# RA8D2_MCU_-_Power.net
KiCad netlist of a schematic drawn in Altium Designer
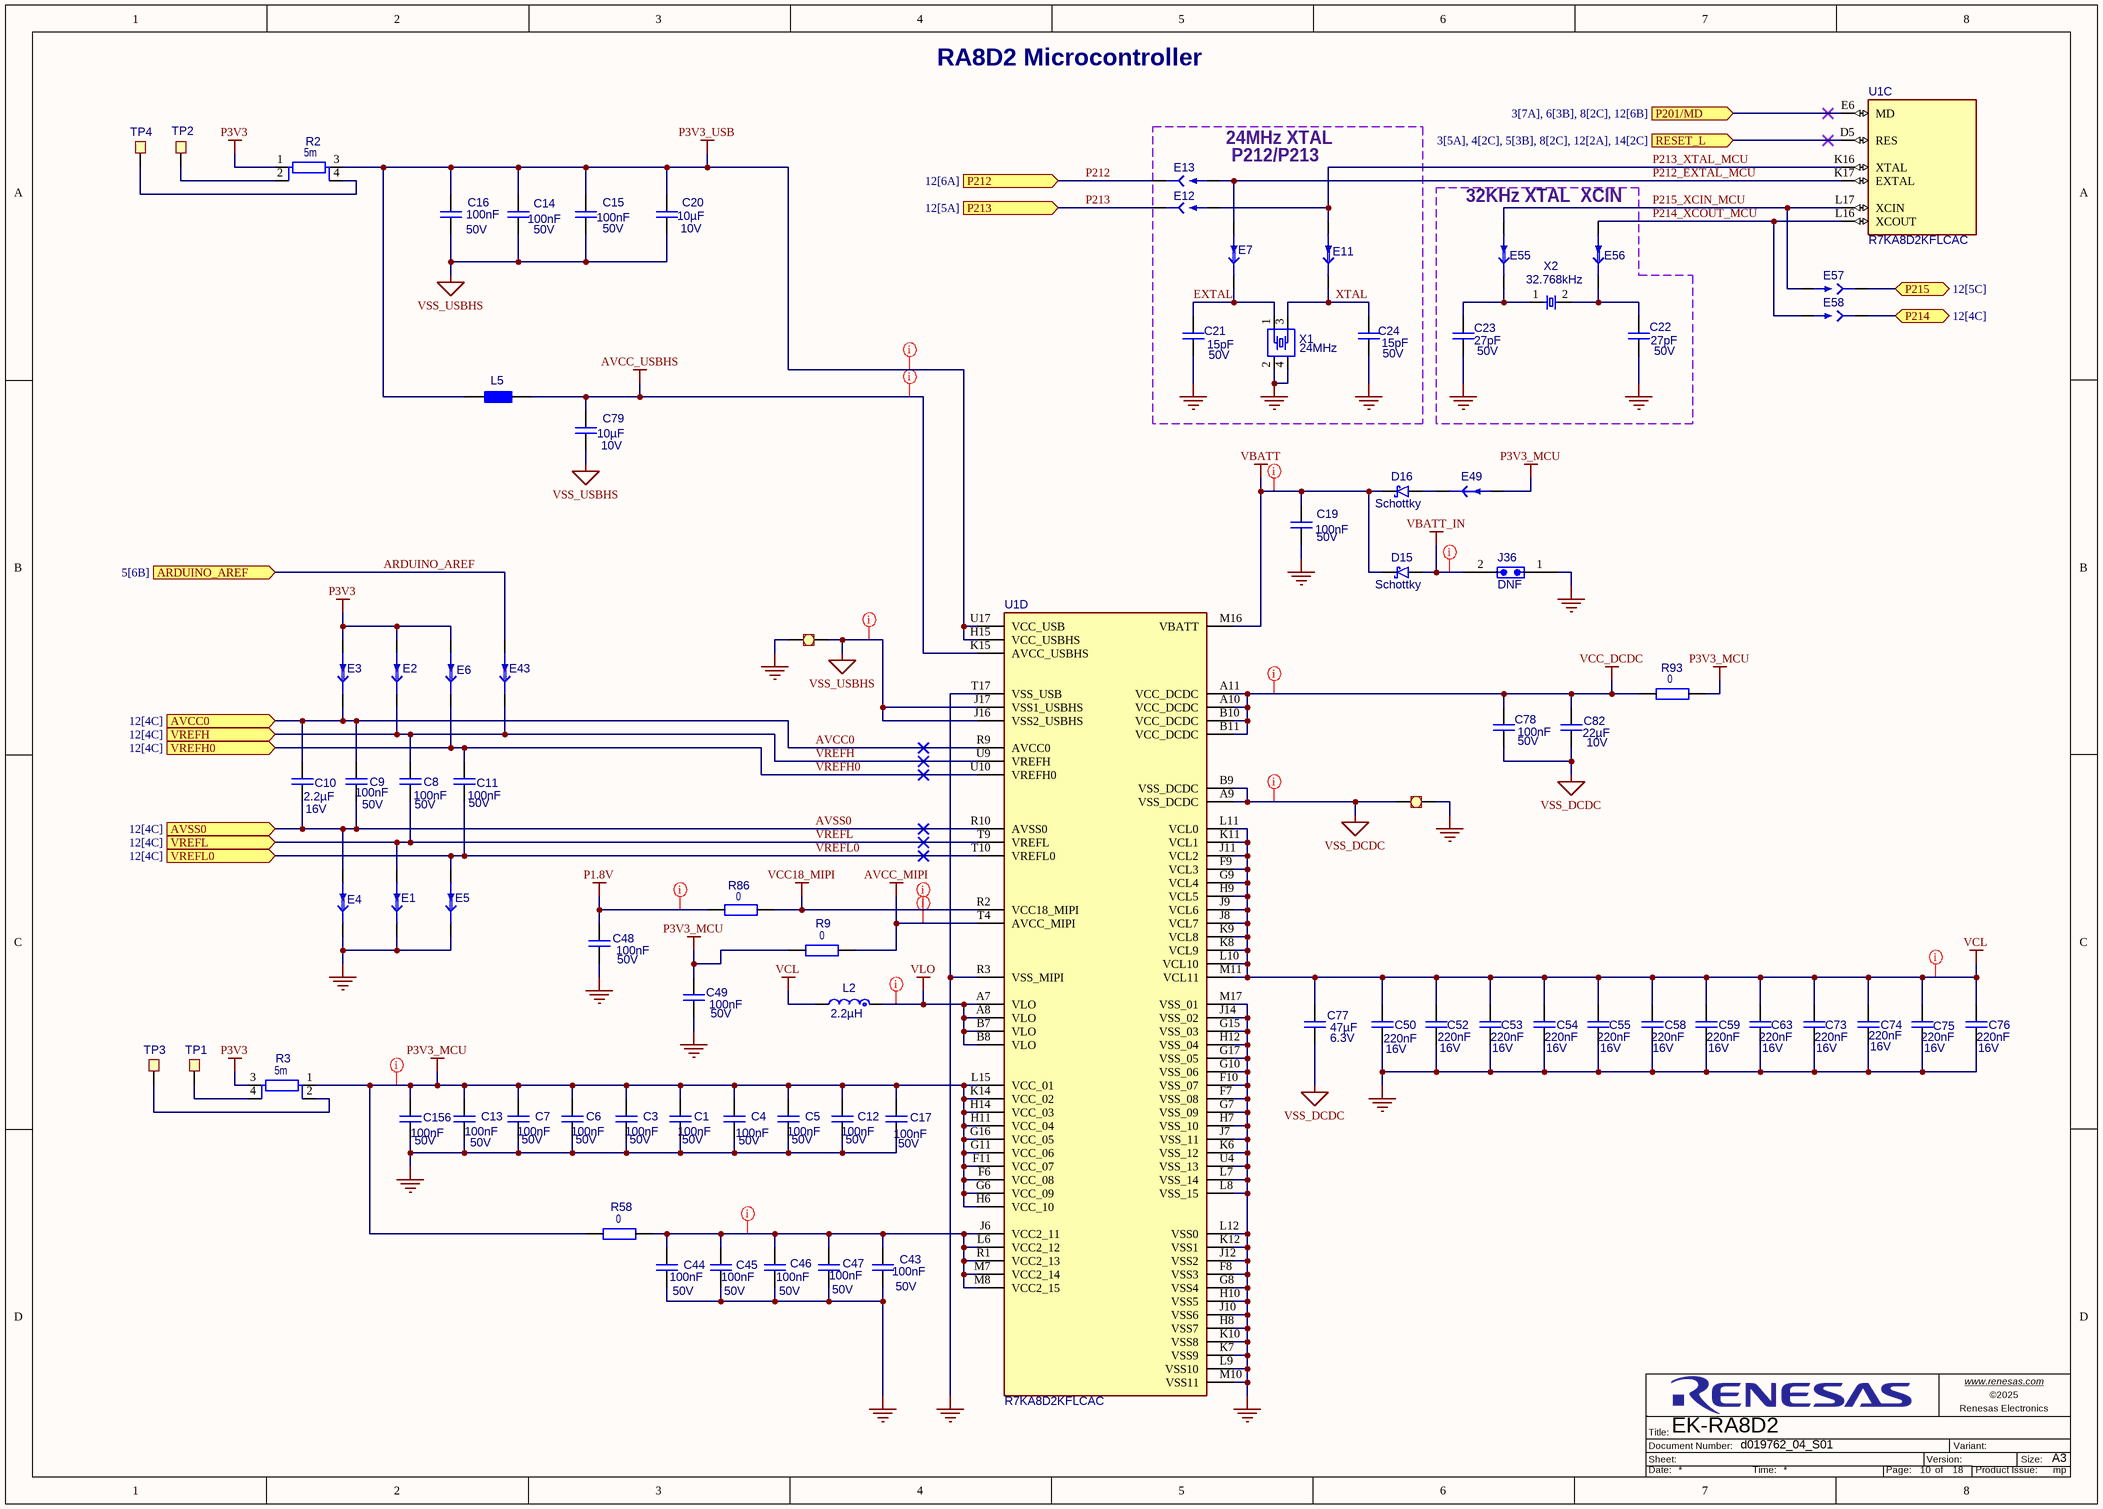
[diagram p0: RA8D2 MCU - Power.SchDoc]

(export (version "E")
  (design (tool "Eeschema 10.0.6"))
  (components
    (comp (ref "C1")
      (value "100nF")
      (footprint "C_EIA0402_0p55")
      (description "Capacitor,EIA0402,100n,50V,X7R")
      (fields
        (field (name "TOLERANCE") "10%")
        (field (name "OPERATING VOLTAGE MAX") "50V")
        (field (name "Comment") "Capacitor")
      )
      (libsource (lib "ek-ra8d2_mp - Customer") (part "Capacitor"))
    )
    (comp (ref "C3")
      (value "100nF")
      (footprint "C_EIA0402_0p55")
      (description "Capacitor,EIA0402,100n,50V,X7R")
      (fields
        (field (name "TOLERANCE") "10%")
        (field (name "OPERATING VOLTAGE MAX") "50V")
        (field (name "Comment") "Capacitor")
      )
      (libsource (lib "ek-ra8d2_mp - Customer") (part "Capacitor"))
    )
    (comp (ref "C4")
      (value "100nF")
      (footprint "C_EIA0402_0p55")
      (description "Capacitor,EIA0402,100n,50V,X7R")
      (fields
        (field (name "TOLERANCE") "10%")
        (field (name "OPERATING VOLTAGE MAX") "50V")
        (field (name "Comment") "Capacitor")
      )
      (libsource (lib "ek-ra8d2_mp - Customer") (part "Capacitor"))
    )
    (comp (ref "C5")
      (value "100nF")
      (footprint "C_EIA0402_0p55")
      (description "Capacitor,EIA0402,100n,50V,X7R")
      (fields
        (field (name "TOLERANCE") "10%")
        (field (name "OPERATING VOLTAGE MAX") "50V")
        (field (name "Comment") "Capacitor")
      )
      (libsource (lib "ek-ra8d2_mp - Customer") (part "Capacitor"))
    )
    (comp (ref "C6")
      (value "100nF")
      (footprint "C_EIA0402_0p55")
      (description "Capacitor,EIA0402,100n,50V,X7R")
      (fields
        (field (name "TOLERANCE") "10%")
        (field (name "OPERATING VOLTAGE MAX") "50V")
        (field (name "Comment") "Capacitor")
      )
      (libsource (lib "ek-ra8d2_mp - Customer") (part "Capacitor"))
    )
    (comp (ref "C7")
      (value "100nF")
      (footprint "C_EIA0402_0p55")
      (description "Capacitor,EIA0402,100n,50V,X7R")
      (fields
        (field (name "TOLERANCE") "10%")
        (field (name "OPERATING VOLTAGE MAX") "50V")
        (field (name "Comment") "Capacitor")
      )
      (libsource (lib "ek-ra8d2_mp - Customer") (part "Capacitor"))
    )
    (comp (ref "C8")
      (value "100nF")
      (footprint "C_EIA0402_0p55")
      (description "Capacitor,EIA0402,100n,50V,X7R")
      (fields
        (field (name "TOLERANCE") "10%")
        (field (name "OPERATING VOLTAGE MAX") "50V")
        (field (name "Comment") "Capacitor")
      )
      (libsource (lib "ek-ra8d2_mp - Customer") (part "Capacitor"))
    )
    (comp (ref "C9")
      (value "100nF")
      (footprint "C_EIA0402_0p55")
      (description "Capacitor,EIA0402,100n,50V,X7R")
      (fields
        (field (name "TOLERANCE") "10%")
        (field (name "OPERATING VOLTAGE MAX") "50V")
        (field (name "Comment") "Capacitor")
      )
      (libsource (lib "ek-ra8d2_mp - Customer") (part "Capacitor"))
    )
    (comp (ref "C10")
      (value "2.2µF")
      (footprint "C_EIA0402_0p7")
      (description "Capacitor,EIA0402,2.2u,16V,X6S")
      (fields
        (field (name "TOLERANCE") "10%")
        (field (name "OPERATING VOLTAGE MAX") "16V")
        (field (name "Comment") "Capacitor")
      )
      (libsource (lib "ek-ra8d2_mp - Customer") (part "Capacitor"))
    )
    (comp (ref "C11")
      (value "100nF")
      (footprint "C_EIA0402_0p55")
      (description "Capacitor,EIA0402,100n,50V,X7R")
      (fields
        (field (name "TOLERANCE") "10%")
        (field (name "OPERATING VOLTAGE MAX") "50V")
        (field (name "Comment") "Capacitor")
      )
      (libsource (lib "ek-ra8d2_mp - Customer") (part "Capacitor"))
    )
    (comp (ref "C12")
      (value "100nF")
      (footprint "C_EIA0402_0p55")
      (description "Capacitor,EIA0402,100n,50V,X7R")
      (fields
        (field (name "TOLERANCE") "10%")
        (field (name "OPERATING VOLTAGE MAX") "50V")
        (field (name "Comment") "Capacitor")
      )
      (libsource (lib "ek-ra8d2_mp - Customer") (part "Capacitor"))
    )
    (comp (ref "C13")
      (value "100nF")
      (footprint "C_EIA0402_0p55")
      (description "Capacitor,EIA0402,100n,50V,X7R")
      (fields
        (field (name "TOLERANCE") "10%")
        (field (name "OPERATING VOLTAGE MAX") "50V")
        (field (name "Comment") "Capacitor")
      )
      (libsource (lib "ek-ra8d2_mp - Customer") (part "Capacitor"))
    )
    (comp (ref "C14")
      (value "100nF")
      (footprint "C_EIA0402_0p55")
      (description "Capacitor,EIA0402,100n,50V,X7R")
      (fields
        (field (name "TOLERANCE") "10%")
        (field (name "OPERATING VOLTAGE MAX") "50V")
        (field (name "Comment") "Capacitor")
      )
      (libsource (lib "ek-ra8d2_mp - Customer") (part "Capacitor"))
    )
    (comp (ref "C15")
      (value "100nF")
      (footprint "C_EIA0402_0p55")
      (description "Capacitor,EIA0402,100n,50V,X7R")
      (fields
        (field (name "TOLERANCE") "10%")
        (field (name "OPERATING VOLTAGE MAX") "50V")
        (field (name "Comment") "Capacitor")
      )
      (libsource (lib "ek-ra8d2_mp - Customer") (part "Capacitor"))
    )
    (comp (ref "C16")
      (value "100nF")
      (footprint "C_EIA0402_0p55")
      (description "Capacitor,EIA0402,100n,50V,X7R")
      (fields
        (field (name "TOLERANCE") "10%")
        (field (name "OPERATING VOLTAGE MAX") "50V")
        (field (name "Comment") "Capacitor")
      )
      (libsource (lib "ek-ra8d2_mp - Customer") (part "Capacitor"))
    )
    (comp (ref "C17")
      (value "100nF")
      (footprint "C_EIA0402_0p55")
      (description "Capacitor,EIA0402,100n,50V,X7R")
      (fields
        (field (name "TOLERANCE") "10%")
        (field (name "OPERATING VOLTAGE MAX") "50V")
        (field (name "Comment") "Capacitor")
      )
      (libsource (lib "ek-ra8d2_mp - Customer") (part "Capacitor"))
    )
    (comp (ref "C19")
      (value "100nF")
      (footprint "C_EIA0402_0p55")
      (description "Capacitor,EIA0402,100n,50V,X7R")
      (fields
        (field (name "TOLERANCE") "10%")
        (field (name "OPERATING VOLTAGE MAX") "50V")
        (field (name "Comment") "Capacitor")
      )
      (libsource (lib "ek-ra8d2_mp - Customer") (part "Capacitor"))
    )
    (comp (ref "C20")
      (value "10µF")
      (footprint "C_EIA0402_0p7")
      (description "Capacitor,EIA0402,10u,10V,X5R")
      (fields
        (field (name "TOLERANCE") "20%")
        (field (name "OPERATING VOLTAGE MAX") "10V")
        (field (name "Comment") "Capacitor")
      )
      (libsource (lib "ek-ra8d2_mp - Customer") (part "Capacitor"))
    )
    (comp (ref "C21")
      (value "15pF")
      (footprint "C_EIA0201_0p4")
      (description "Capacitor,EIA0201,15p,50V,C0G")
      (fields
        (field (name "TOLERANCE") "1%")
        (field (name "OPERATING VOLTAGE MAX") "50V")
        (field (name "Comment") "Capacitor")
      )
      (libsource (lib "ek-ra8d2_mp - Customer") (part "Capacitor"))
    )
    (comp (ref "C22")
      (value "27pF")
      (footprint "C_EIA0402_0p55")
      (description "Capacitor,EIA0402,27p,50V,C0G")
      (fields
        (field (name "TOLERANCE") "5%")
        (field (name "OPERATING VOLTAGE MAX") "50V")
        (field (name "Comment") "Capacitor")
      )
      (libsource (lib "ek-ra8d2_mp - Customer") (part "Capacitor"))
    )
    (comp (ref "C23")
      (value "27pF")
      (footprint "C_EIA0402_0p55")
      (description "Capacitor,EIA0402,27p,50V,C0G")
      (fields
        (field (name "TOLERANCE") "5%")
        (field (name "OPERATING VOLTAGE MAX") "50V")
        (field (name "Comment") "Capacitor")
      )
      (libsource (lib "ek-ra8d2_mp - Customer") (part "Capacitor"))
    )
    (comp (ref "C24")
      (value "15pF")
      (footprint "C_EIA0201_0p4")
      (description "Capacitor,EIA0201,15p,50V,C0G")
      (fields
        (field (name "TOLERANCE") "1%")
        (field (name "OPERATING VOLTAGE MAX") "50V")
        (field (name "Comment") "Capacitor")
      )
      (libsource (lib "ek-ra8d2_mp - Customer") (part "Capacitor"))
    )
    (comp (ref "C43")
      (value "100nF")
      (footprint "C_EIA0402_0p55")
      (description "Capacitor,EIA0402,100n,50V,X7R")
      (fields
        (field (name "TOLERANCE") "10%")
        (field (name "OPERATING VOLTAGE MAX") "50V")
        (field (name "Comment") "Capacitor")
      )
      (libsource (lib "ek-ra8d2_mp - Customer") (part "Capacitor"))
    )
    (comp (ref "C44")
      (value "100nF")
      (footprint "C_EIA0402_0p55")
      (description "Capacitor,EIA0402,100n,50V,X7R")
      (fields
        (field (name "TOLERANCE") "10%")
        (field (name "OPERATING VOLTAGE MAX") "50V")
        (field (name "Comment") "Capacitor")
      )
      (libsource (lib "ek-ra8d2_mp - Customer") (part "Capacitor"))
    )
    (comp (ref "C45")
      (value "100nF")
      (footprint "C_EIA0402_0p55")
      (description "Capacitor,EIA0402,100n,50V,X7R")
      (fields
        (field (name "TOLERANCE") "10%")
        (field (name "OPERATING VOLTAGE MAX") "50V")
        (field (name "Comment") "Capacitor")
      )
      (libsource (lib "ek-ra8d2_mp - Customer") (part "Capacitor"))
    )
    (comp (ref "C46")
      (value "100nF")
      (footprint "C_EIA0402_0p55")
      (description "Capacitor,EIA0402,100n,50V,X7R")
      (fields
        (field (name "TOLERANCE") "10%")
        (field (name "OPERATING VOLTAGE MAX") "50V")
        (field (name "Comment") "Capacitor")
      )
      (libsource (lib "ek-ra8d2_mp - Customer") (part "Capacitor"))
    )
    (comp (ref "C47")
      (value "100nF")
      (footprint "C_EIA0402_0p55")
      (description "Capacitor,EIA0402,100n,50V,X7R")
      (fields
        (field (name "TOLERANCE") "10%")
        (field (name "OPERATING VOLTAGE MAX") "50V")
        (field (name "Comment") "Capacitor")
      )
      (libsource (lib "ek-ra8d2_mp - Customer") (part "Capacitor"))
    )
    (comp (ref "C48")
      (value "100nF")
      (footprint "C_EIA0402_0p55")
      (description "Capacitor,EIA0402,100n,50V,X7R")
      (fields
        (field (name "TOLERANCE") "10%")
        (field (name "OPERATING VOLTAGE MAX") "50V")
        (field (name "Comment") "Capacitor")
      )
      (libsource (lib "ek-ra8d2_mp - Customer") (part "Capacitor"))
    )
    (comp (ref "C49")
      (value "100nF")
      (footprint "C_EIA0402_0p55")
      (description "Capacitor,EIA0402,100n,50V,X7R")
      (fields
        (field (name "TOLERANCE") "10%")
        (field (name "OPERATING VOLTAGE MAX") "50V")
        (field (name "Comment") "Capacitor")
      )
      (libsource (lib "ek-ra8d2_mp - Customer") (part "Capacitor"))
    )
    (comp (ref "C50")
      (value "220nF")
      (footprint "C_EIA0402_0p55")
      (description "Capacitor,EIA0402,220n,16V,X7R")
      (fields
        (field (name "TOLERANCE") "10%")
        (field (name "OPERATING VOLTAGE MAX") "16V")
        (field (name "Comment") "Capacitor")
      )
      (libsource (lib "ek-ra8d2_mp - Customer") (part "Capacitor"))
    )
    (comp (ref "C52")
      (value "220nF")
      (footprint "C_EIA0402_0p55")
      (description "Capacitor,EIA0402,220n,16V,X7R")
      (fields
        (field (name "TOLERANCE") "10%")
        (field (name "OPERATING VOLTAGE MAX") "16V")
        (field (name "Comment") "Capacitor")
      )
      (libsource (lib "ek-ra8d2_mp - Customer") (part "Capacitor"))
    )
    (comp (ref "C53")
      (value "220nF")
      (footprint "C_EIA0402_0p55")
      (description "Capacitor,EIA0402,220n,16V,X7R")
      (fields
        (field (name "TOLERANCE") "10%")
        (field (name "OPERATING VOLTAGE MAX") "16V")
        (field (name "Comment") "Capacitor")
      )
      (libsource (lib "ek-ra8d2_mp - Customer") (part "Capacitor"))
    )
    (comp (ref "C54")
      (value "220nF")
      (footprint "C_EIA0402_0p55")
      (description "Capacitor,EIA0402,220n,16V,X7R")
      (fields
        (field (name "TOLERANCE") "10%")
        (field (name "OPERATING VOLTAGE MAX") "16V")
        (field (name "Comment") "Capacitor")
      )
      (libsource (lib "ek-ra8d2_mp - Customer") (part "Capacitor"))
    )
    (comp (ref "C55")
      (value "220nF")
      (footprint "C_EIA0402_0p55")
      (description "Capacitor,EIA0402,220n,16V,X7R")
      (fields
        (field (name "TOLERANCE") "10%")
        (field (name "OPERATING VOLTAGE MAX") "16V")
        (field (name "Comment") "Capacitor")
      )
      (libsource (lib "ek-ra8d2_mp - Customer") (part "Capacitor"))
    )
    (comp (ref "C58")
      (value "220nF")
      (footprint "C_EIA0402_0p55")
      (description "Capacitor,EIA0402,220n,16V,X7R")
      (fields
        (field (name "TOLERANCE") "10%")
        (field (name "OPERATING VOLTAGE MAX") "16V")
        (field (name "Comment") "Capacitor")
      )
      (libsource (lib "ek-ra8d2_mp - Customer") (part "Capacitor"))
    )
    (comp (ref "C59")
      (value "220nF")
      (footprint "C_EIA0402_0p55")
      (description "Capacitor,EIA0402,220n,16V,X7R")
      (fields
        (field (name "TOLERANCE") "10%")
        (field (name "OPERATING VOLTAGE MAX") "16V")
        (field (name "Comment") "Capacitor")
      )
      (libsource (lib "ek-ra8d2_mp - Customer") (part "Capacitor"))
    )
    (comp (ref "C63")
      (value "220nF")
      (footprint "C_EIA0402_0p55")
      (description "Capacitor,EIA0402,220n,16V,X7R")
      (fields
        (field (name "TOLERANCE") "10%")
        (field (name "OPERATING VOLTAGE MAX") "16V")
        (field (name "Comment") "Capacitor")
      )
      (libsource (lib "ek-ra8d2_mp - Customer") (part "Capacitor"))
    )
    (comp (ref "C73")
      (value "220nF")
      (footprint "C_EIA0402_0p55")
      (description "Capacitor,EIA0402,220n,16V,X7R")
      (fields
        (field (name "TOLERANCE") "10%")
        (field (name "OPERATING VOLTAGE MAX") "16V")
        (field (name "Comment") "Capacitor")
      )
      (libsource (lib "ek-ra8d2_mp - Customer") (part "Capacitor"))
    )
    (comp (ref "C74")
      (value "220nF")
      (footprint "C_EIA0402_0p55")
      (description "Capacitor,EIA0402,220n,16V,X7R")
      (fields
        (field (name "TOLERANCE") "10%")
        (field (name "OPERATING VOLTAGE MAX") "16V")
        (field (name "Comment") "Capacitor")
      )
      (libsource (lib "ek-ra8d2_mp - Customer") (part "Capacitor"))
    )
    (comp (ref "C75")
      (value "220nF")
      (footprint "C_EIA0402_0p55")
      (description "Capacitor,EIA0402,220n,16V,X7R")
      (fields
        (field (name "TOLERANCE") "10%")
        (field (name "OPERATING VOLTAGE MAX") "16V")
        (field (name "Comment") "Capacitor")
      )
      (libsource (lib "ek-ra8d2_mp - Customer") (part "Capacitor"))
    )
    (comp (ref "C76")
      (value "220nF")
      (footprint "C_EIA0402_0p55")
      (description "Capacitor,EIA0402,220n,16V,X7R")
      (fields
        (field (name "TOLERANCE") "10%")
        (field (name "OPERATING VOLTAGE MAX") "16V")
        (field (name "Comment") "Capacitor")
      )
      (libsource (lib "ek-ra8d2_mp - Customer") (part "Capacitor"))
    )
    (comp (ref "C77")
      (value "47µF")
      (footprint "C_EIA1206_1p8")
      (description "Capacitor,EIA1206,47u,6.3V,X7U")
      (fields
        (field (name "OPERATING VOLTAGE MAX") "6.3V")
        (field (name "TOLERANCE") "20%")
        (field (name "Comment") "GRM31CE70J476ME15L")
      )
      (libsource (lib "ek-ra8d2_mp - Customer") (part "Capacitor"))
    )
    (comp (ref "C78")
      (value "100nF")
      (footprint "C_EIA0402_0p55")
      (description "Capacitor,EIA0402,100n,50V,X7R")
      (fields
        (field (name "TOLERANCE") "10%")
        (field (name "OPERATING VOLTAGE MAX") "50V")
        (field (name "Comment") "Capacitor")
      )
      (libsource (lib "ek-ra8d2_mp - Customer") (part "Capacitor"))
    )
    (comp (ref "C79")
      (value "10µF")
      (footprint "C_EIA0402_0p7")
      (description "Capacitor,EIA0402,10u,10V,X5R")
      (fields
        (field (name "TOLERANCE") "20%")
        (field (name "OPERATING VOLTAGE MAX") "10V")
        (field (name "Comment") "Capacitor")
      )
      (libsource (lib "ek-ra8d2_mp - Customer") (part "Capacitor"))
    )
    (comp (ref "C82")
      (value "22µF")
      (footprint "C_EIA1206_1p8")
      (description "Capacitor,EIA1206,22u,10V,X7R")
      (fields
        (field (name "TOLERANCE") "10%")
        (field (name "OPERATING VOLTAGE MAX") "10V")
        (field (name "Comment") "Capacitor")
      )
      (libsource (lib "ek-ra8d2_mp - Customer") (part "Capacitor"))
    )
    (comp (ref "C156")
      (value "100nF")
      (footprint "C_EIA0402_0p55")
      (description "Capacitor,EIA0402,100n,50V,X7R")
      (fields
        (field (name "TOLERANCE") "10%")
        (field (name "OPERATING VOLTAGE MAX") "50V")
        (field (name "Comment") "Capacitor")
      )
      (libsource (lib "ek-ra8d2_mp - Customer") (part "Capacitor"))
    )
    (comp (ref "D15")
      (value "Schottky")
      (footprint "roh_sod-123fl_pmdu")
      (description "Rectifier Diode, Schottky, 1 Phase, 1 Element, 1A, 40V V(RRM), Silicon")
      (libsource (lib "ek-ra8d2_mp - Customer") (part "Schottky"))
    )
    (comp (ref "D16")
      (value "Schottky")
      (footprint "roh_sod-123fl_pmdu")
      (description "Rectifier Diode, Schottky, 1 Phase, 1 Element, 1A, 40V V(RRM), Silicon")
      (libsource (lib "ek-ra8d2_mp - Customer") (part "Schottky"))
    )
    (comp (ref "E1")
      (value "TRACE_CUT_0805")
      (footprint "trace_cut_0805")
      (description "Trace Cut, SMD, 0805 size")
      (libsource (lib "ek-ra8d2_mp - Customer") (part "trace_cut"))
    )
    (comp (ref "E2")
      (value "TRACE_CUT_0805")
      (footprint "trace_cut_0805")
      (description "Trace Cut, SMD, 0805 size")
      (libsource (lib "ek-ra8d2_mp - Customer") (part "trace_cut"))
    )
    (comp (ref "E3")
      (value "TRACE_CUT_0805")
      (footprint "trace_cut_0805")
      (description "Trace Cut, SMD, 0805 size")
      (libsource (lib "ek-ra8d2_mp - Customer") (part "trace_cut"))
    )
    (comp (ref "E4")
      (value "TRACE_CUT_0805")
      (footprint "trace_cut_0805")
      (description "Trace Cut, SMD, 0805 size")
      (libsource (lib "ek-ra8d2_mp - Customer") (part "trace_cut"))
    )
    (comp (ref "E5")
      (value "TRACE_CUT_0805")
      (footprint "trace_cut_0805")
      (description "Trace Cut, SMD, 0805 size")
      (libsource (lib "ek-ra8d2_mp - Customer") (part "trace_cut"))
    )
    (comp (ref "E6")
      (value "TRACE_CUT_0805")
      (footprint "trace_cut_0805")
      (description "Trace Cut, SMD, 0805 size")
      (libsource (lib "ek-ra8d2_mp - Customer") (part "trace_cut"))
    )
    (comp (ref "E7")
      (value "TRACE_CUT_0805")
      (footprint "trace_cut_0805")
      (description "Trace Cut, SMD, 0805 size")
      (libsource (lib "ek-ra8d2_mp - Customer") (part "trace_cut"))
    )
    (comp (ref "E11")
      (value "TRACE_CUT_0805")
      (footprint "trace_cut_0805")
      (description "Trace Cut, SMD, 0805 size")
      (libsource (lib "ek-ra8d2_mp - Customer") (part "trace_cut"))
    )
    (comp (ref "E12")
      (value "SOLDER_BRIDGE_0805")
      (footprint "solder_bridge_0805")
      (description "Solder Bridge, SMD, 0805 size")
      (libsource (lib "ek-ra8d2_mp - Customer") (part "solder_bridge"))
    )
    (comp (ref "E13")
      (value "SOLDER_BRIDGE_0805")
      (footprint "solder_bridge_0805")
      (description "Solder Bridge, SMD, 0805 size")
      (libsource (lib "ek-ra8d2_mp - Customer") (part "solder_bridge"))
    )
    (comp (ref "E43")
      (value "TRACE_CUT_0805")
      (footprint "trace_cut_0805")
      (description "Trace Cut, SMD, 0805 size")
      (libsource (lib "ek-ra8d2_mp - Customer") (part "trace_cut"))
    )
    (comp (ref "E49")
      (value "TRACE_CUT_0805")
      (footprint "trace_cut_0805")
      (description "Trace Cut, SMD, 0805 size")
      (libsource (lib "ek-ra8d2_mp - Customer") (part "trace_cut"))
    )
    (comp (ref "E55")
      (value "TRACE_CUT_0805")
      (footprint "trace_cut_0805")
      (description "Trace Cut, SMD, 0805 size")
      (libsource (lib "ek-ra8d2_mp - Customer") (part "trace_cut"))
    )
    (comp (ref "E56")
      (value "TRACE_CUT_0805")
      (footprint "trace_cut_0805")
      (description "Trace Cut, SMD, 0805 size")
      (libsource (lib "ek-ra8d2_mp - Customer") (part "trace_cut"))
    )
    (comp (ref "E57")
      (value "SOLDER_BRIDGE_0805")
      (footprint "solder_bridge_0805")
      (description "Solder Bridge, SMD, 0805 size")
      (libsource (lib "ek-ra8d2_mp - Customer") (part "solder_bridge"))
    )
    (comp (ref "E58")
      (value "SOLDER_BRIDGE_0805")
      (footprint "solder_bridge_0805")
      (description "Solder Bridge, SMD, 0805 size")
      (libsource (lib "ek-ra8d2_mp - Customer") (part "solder_bridge"))
    )
    (comp (ref "FS1")
      (value "FS_Trace_120um")
      (footprint "force_sense_120um")
      (description "Force-Sense Trace 120um")
      (libsource (lib "ek-ra8d2_mp - Customer") (part "force_sense"))
    )
    (comp (ref "FS2")
      (value "FS_Trace_120um")
      (footprint "force_sense_120um")
      (description "Force-Sense Trace 120um")
      (libsource (lib "ek-ra8d2_mp - Customer") (part "force_sense"))
    )
    (comp (ref "J36")
      (value "CON_002")
      (footprint "wue_61300211121")
      (description "Header,2way,1row,vertical,2.54mm,THT")
      (fields (field (name "DNF") "DNF"))
      (libsource (lib "ek-ra8d2_mp - Customer") (part "CON_002"))
    )
    (comp (ref "L2")
      (value "2.2µH")
      (footprint "tdk_spm5020-lr")
      (description "Inductor, 2.2uH, 20%, 7A, Metal-Core")
      (fields (field (name "TOLERANCE") "20%") (field (name "Comment") "Inductor"))
      (libsource (lib "ek-ra8d2_mp - Customer") (part "Inductor"))
    )
    (comp (ref "L5")
      (value "MPZ1005S121CT000")
      (footprint "L_EIA0402")
      (description "Ferrite Chip, 1.2A, 90mOhm DCR, 120Ohm Impedance @100MHz")
      (fields (field (name "TOLERANCE") "25%"))
      (libsource (lib "ek-ra8d2_mp - Customer") (part "Ferrite"))
    )
    (comp (ref "R2")
      (value "5m")
      (footprint "R_EIA0612")
      (description "Current Sense Resistor,EIA0612,5m,1W")
      (fields (field (name "TOLERANCE") "1%") (field (name "POWER") "1W"))
      (libsource (lib "") (part "Current_Sense_Resistor_1"))
    )
    (comp (ref "R3")
      (value "5m")
      (footprint "R_EIA0612")
      (description "Current Sense Resistor,EIA0612,5m,1W")
      (fields (field (name "TOLERANCE") "1%") (field (name "POWER") "1W"))
      (libsource (lib "ek-ra8d2_mp - Customer") (part "Current_Sense_Resistor"))
    )
    (comp (ref "R9")
      (value "0")
      (footprint "R_EIA1206")
      (description "Resistor,EIA1206,0,0.25W")
      (fields (field (name "POWER") "250mW") (field (name "TOLERANCE") "5%"))
      (libsource (lib "ek-ra8d2_mp - Customer") (part "Resistor"))
    )
    (comp (ref "R58")
      (value "0")
      (footprint "R_EIA1206")
      (description "Resistor,EIA1206,0,0.25W")
      (fields (field (name "POWER") "250mW") (field (name "TOLERANCE") "5%"))
      (libsource (lib "") (part "Resistor_1"))
    )
    (comp (ref "R86")
      (value "0")
      (footprint "R_EIA1206")
      (description "Resistor,EIA1206,0,0.25W")
      (fields (field (name "POWER") "250mW") (field (name "TOLERANCE") "5%"))
      (libsource (lib "ek-ra8d2_mp - Customer") (part "Resistor"))
    )
    (comp (ref "R93")
      (value "0")
      (footprint "R_EIA1206")
      (description "Resistor,EIA1206,0,0.25W")
      (fields (field (name "POWER") "250mW") (field (name "TOLERANCE") "5%"))
      (libsource (lib "ek-ra8d2_mp - Customer") (part "Resistor"))
    )
    (comp (ref "TP1")
      (value "TP_Mini")
      (footprint "key_5019")
      (description "Testpoint Miniature")
      (libsource (lib "ek-ra8d2_mp - Customer") (part "tp_clip"))
    )
    (comp (ref "TP2")
      (value "TP_Mini")
      (footprint "key_5019")
      (description "Testpoint Miniature")
      (libsource (lib "ek-ra8d2_mp - Customer") (part "tp_clip"))
    )
    (comp (ref "TP3")
      (value "TP_Mini")
      (footprint "key_5019")
      (description "Testpoint Miniature")
      (libsource (lib "ek-ra8d2_mp - Customer") (part "tp_clip"))
    )
    (comp (ref "TP4")
      (value "TP_Mini")
      (footprint "key_5019")
      (description "Testpoint Miniature")
      (libsource (lib "ek-ra8d2_mp - Customer") (part "tp_clip"))
    )
    (comp (ref "U1")
      (value "R7KA8D2KFLCAC")
      (footprint "ren_bga289_PRBG0289JA-A")
      (libsource (lib "ek-ra8d2_mp - Customer") (part "ren_R7KA8D2KFLCAC"))
    )
    (comp (ref "X1")
      (value "24MHz")
      (footprint "dio_FL")
      (description "Crystal, 24MHz, 10pF, 3.2x2.5")
      (fields (field (name "TOLERANCE") "10ppm") (field (name "Comment") "FL2400022"))
      (libsource (lib "ek-ra8d2_mp - Customer") (part "Crystal_4pin"))
    )
    (comp (ref "X2")
      (value "32.768kHz")
      (footprint "ABR_ABS07")
      (description "Crystal, 32.768kHz, 12.5pF, 3.2x1.5")
      (fields (field (name "TOLERANCE") "10ppm") (field (name "Comment") "ABS07-32.768KHZ-1-T"))
      (libsource (lib "ek-ra8d2_mp - Customer") (part "Crystal_2pin"))
    )
  )
  (nets
    (net (code "1") (name "/ARDUINO_AREF") (class "Default")
      (node (ref "E43") (pin "2") (pinfunction "2_2") (pintype "passive"))
    )
    (net (code "2") (name "/AVCC0") (class "Default")
      (node (ref "C10") (pin "2") (pinfunction "2_2") (pintype "passive"))
      (node (ref "C9") (pin "1") (pinfunction "1_1") (pintype "passive"))
      (node (ref "E3") (pin "1") (pinfunction "1_1") (pintype "passive"))
      (node (ref "U1") (pin "R9") (pinfunction "AVCC0_R9") (pintype "power_in"))
    )
    (net (code "3") (name "/AVSS0") (class "Default")
      (node (ref "C10") (pin "1") (pinfunction "1_1") (pintype "passive"))
      (node (ref "C9") (pin "2") (pinfunction "2_2") (pintype "passive"))
      (node (ref "E4") (pin "2") (pinfunction "2_2") (pintype "passive"))
      (node (ref "U1") (pin "R10") (pinfunction "AVSS0_R10") (pintype "power_in"))
    )
    (net (code "4") (name "/EXTAL") (class "Default")
      (node (ref "C21") (pin "1") (pinfunction "1_1") (pintype "passive"))
      (node (ref "E7") (pin "1") (pinfunction "1_1") (pintype "passive"))
      (node (ref "X1") (pin "1") (pinfunction "1_1") (pintype "passive"))
    )
    (net (code "5") (name "/P201{slash}MD") (class "Default")
      (node (ref "U1") (pin "E6") (pinfunction "MD_E6") (pintype "bidirectional"))
    )
    (net (code "6") (name "/P212") (class "Default")
      (node (ref "E13") (pin "1") (pinfunction "1_1") (pintype "passive"))
    )
    (net (code "7") (name "/P212_EXTAL_MCU") (class "Default")
      (node (ref "E13") (pin "2") (pinfunction "2_2") (pintype "passive"))
      (node (ref "E7") (pin "2") (pinfunction "2_2") (pintype "passive"))
      (node (ref "U1") (pin "K17") (pinfunction "EXTAL_K17") (pintype "bidirectional"))
    )
    (net (code "8") (name "/P213") (class "Default")
      (node (ref "E12") (pin "1") (pinfunction "1_1") (pintype "passive"))
    )
    (net (code "9") (name "/P213_XTAL_MCU") (class "Default")
      (node (ref "E11") (pin "2") (pinfunction "2_2") (pintype "passive"))
      (node (ref "E12") (pin "2") (pinfunction "2_2") (pintype "passive"))
      (node (ref "U1") (pin "K16") (pinfunction "XTAL_K16") (pintype "bidirectional"))
    )
    (net (code "10") (name "/P214") (class "Default")
      (node (ref "E58") (pin "1") (pinfunction "1_1") (pintype "passive"))
    )
    (net (code "11") (name "/P214_XCOUT_MCU") (class "Default")
      (node (ref "E56") (pin "2") (pinfunction "2_2") (pintype "passive"))
      (node (ref "E58") (pin "2") (pinfunction "2_2") (pintype "passive"))
      (node (ref "U1") (pin "L16") (pinfunction "XCOUT_L16") (pintype "bidirectional"))
    )
    (net (code "12") (name "/P215") (class "Default")
      (node (ref "E57") (pin "1") (pinfunction "1_1") (pintype "passive"))
    )
    (net (code "13") (name "/P215_XCIN_MCU") (class "Default")
      (node (ref "E55") (pin "2") (pinfunction "2_2") (pintype "passive"))
      (node (ref "E57") (pin "2") (pinfunction "2_2") (pintype "passive"))
      (node (ref "U1") (pin "L17") (pinfunction "XCIN_L17") (pintype "bidirectional"))
    )
    (net (code "14") (name "/RESET_L") (class "Default")
      (node (ref "U1") (pin "D5") (pinfunction "RES_D5") (pintype "bidirectional"))
    )
    (net (code "15") (name "/VREFH") (class "Default")
      (node (ref "C8") (pin "1") (pinfunction "1_1") (pintype "passive"))
      (node (ref "E2") (pin "1") (pinfunction "1_1") (pintype "passive"))
      (node (ref "E43") (pin "1") (pinfunction "1_1") (pintype "passive"))
      (node (ref "U1") (pin "U9") (pinfunction "VREFH_U9") (pintype "power_in"))
    )
    (net (code "16") (name "/VREFH0") (class "Default")
      (node (ref "C11") (pin "1") (pinfunction "1_1") (pintype "passive"))
      (node (ref "E6") (pin "1") (pinfunction "1_1") (pintype "passive"))
      (node (ref "U1") (pin "U10") (pinfunction "VREFH0_U10") (pintype "power_in"))
    )
    (net (code "17") (name "/VREFL") (class "Default")
      (node (ref "C8") (pin "2") (pinfunction "2_2") (pintype "passive"))
      (node (ref "E1") (pin "2") (pinfunction "2_2") (pintype "passive"))
      (node (ref "U1") (pin "T9") (pinfunction "VREFL_T9") (pintype "power_in"))
    )
    (net (code "18") (name "/VREFL0") (class "Default")
      (node (ref "C11") (pin "2") (pinfunction "2_2") (pintype "passive"))
      (node (ref "E5") (pin "2") (pinfunction "2_2") (pintype "passive"))
      (node (ref "U1") (pin "T10") (pinfunction "VREFL0_T10") (pintype "power_in"))
    )
    (net (code "19") (name "/XTAL") (class "Default")
      (node (ref "C24") (pin "1") (pinfunction "1_1") (pintype "passive"))
      (node (ref "E11") (pin "1") (pinfunction "1_1") (pintype "passive"))
      (node (ref "X1") (pin "3") (pinfunction "3_3") (pintype "passive"))
    )
    (net (code "20") (name "AVCC_MIPI") (class "Default")
      (node (ref "R9") (pin "2") (pinfunction "2_2") (pintype "passive"))
      (node (ref "U1") (pin "T4") (pinfunction "AVCC_MIPI_T4") (pintype "power_in"))
    )
    (net (code "21") (name "AVCC_USBHS") (class "Default")
      (node (ref "C79") (pin "1") (pinfunction "1_1") (pintype "passive"))
      (node (ref "L5") (pin "1") (pinfunction "1_1") (pintype "passive"))
      (node (ref "U1") (pin "K15") (pinfunction "AVCC_USBHS_K15") (pintype "passive"))
    )
    (net (code "22") (name "GND") (class "Default")
      (node (ref "C1") (pin "1") (pinfunction "1_1") (pintype "passive"))
      (node (ref "C12") (pin "1") (pinfunction "1_1") (pintype "passive"))
      (node (ref "C13") (pin "1") (pinfunction "1_1") (pintype "passive"))
      (node (ref "C156") (pin "1") (pinfunction "1_1") (pintype "passive"))
      (node (ref "C17") (pin "1") (pinfunction "1_1") (pintype "passive"))
      (node (ref "C19") (pin "2") (pinfunction "2_2") (pintype "passive"))
      (node (ref "C21") (pin "2") (pinfunction "2_2") (pintype "passive"))
      (node (ref "C22") (pin "2") (pinfunction "2_2") (pintype "passive"))
      (node (ref "C23") (pin "2") (pinfunction "2_2") (pintype "passive"))
      (node (ref "C24") (pin "2") (pinfunction "2_2") (pintype "passive"))
      (node (ref "C3") (pin "1") (pinfunction "1_1") (pintype "passive"))
      (node (ref "C4") (pin "1") (pinfunction "1_1") (pintype "passive"))
      (node (ref "C43") (pin "1") (pinfunction "1_1") (pintype "passive"))
      (node (ref "C44") (pin "1") (pinfunction "1_1") (pintype "passive"))
      (node (ref "C45") (pin "1") (pinfunction "1_1") (pintype "passive"))
      (node (ref "C46") (pin "1") (pinfunction "1_1") (pintype "passive"))
      (node (ref "C47") (pin "1") (pinfunction "1_1") (pintype "passive"))
      (node (ref "C48") (pin "2") (pinfunction "2_2") (pintype "passive"))
      (node (ref "C49") (pin "2") (pinfunction "2_2") (pintype "passive"))
      (node (ref "C5") (pin "1") (pinfunction "1_1") (pintype "passive"))
      (node (ref "C50") (pin "2") (pinfunction "2_2") (pintype "passive"))
      (node (ref "C52") (pin "2") (pinfunction "2_2") (pintype "passive"))
      (node (ref "C53") (pin "2") (pinfunction "2_2") (pintype "passive"))
      (node (ref "C54") (pin "2") (pinfunction "2_2") (pintype "passive"))
      (node (ref "C55") (pin "2") (pinfunction "2_2") (pintype "passive"))
      (node (ref "C58") (pin "2") (pinfunction "2_2") (pintype "passive"))
      (node (ref "C59") (pin "2") (pinfunction "2_2") (pintype "passive"))
      (node (ref "C6") (pin "1") (pinfunction "1_1") (pintype "passive"))
      (node (ref "C63") (pin "2") (pinfunction "2_2") (pintype "passive"))
      (node (ref "C7") (pin "1") (pinfunction "1_1") (pintype "passive"))
      (node (ref "C73") (pin "2") (pinfunction "2_2") (pintype "passive"))
      (node (ref "C74") (pin "2") (pinfunction "2_2") (pintype "passive"))
      (node (ref "C75") (pin "2") (pinfunction "2_2") (pintype "passive"))
      (node (ref "C76") (pin "2") (pinfunction "2_2") (pintype "passive"))
      (node (ref "E1") (pin "1") (pinfunction "1_1") (pintype "passive"))
      (node (ref "E4") (pin "1") (pinfunction "1_1") (pintype "passive"))
      (node (ref "E5") (pin "1") (pinfunction "1_1") (pintype "passive"))
      (node (ref "FS1") (pin "1") (pinfunction "1_1") (pintype "passive"))
      (node (ref "FS2") (pin "2") (pinfunction "2_2") (pintype "passive"))
      (node (ref "J36") (pin "1") (pinfunction "1_1") (pintype "passive"))
      (node (ref "U1") (pin "F10") (pinfunction "VSS_07_F10") (pintype "power_in"))
      (node (ref "U1") (pin "F7") (pinfunction "VSS_08_F7") (pintype "power_in"))
      (node (ref "U1") (pin "F8") (pinfunction "VSS3_F8") (pintype "power_in"))
      (node (ref "U1") (pin "G10") (pinfunction "VSS_06_G10") (pintype "power_in"))
      (node (ref "U1") (pin "G15") (pinfunction "VSS_03_G15") (pintype "power_in"))
      (node (ref "U1") (pin "G17") (pinfunction "VSS_05_G17") (pintype "power_in"))
      (node (ref "U1") (pin "G7") (pinfunction "VSS_09_G7") (pintype "power_in"))
      (node (ref "U1") (pin "G8") (pinfunction "VSS4_G8") (pintype "power_in"))
      (node (ref "U1") (pin "H10") (pinfunction "VSS5_H10") (pintype "power_in"))
      (node (ref "U1") (pin "H12") (pinfunction "VSS_04_H12") (pintype "power_in"))
      (node (ref "U1") (pin "H7") (pinfunction "VSS_10_H7") (pintype "power_in"))
      (node (ref "U1") (pin "H8") (pinfunction "VSS7_H8") (pintype "power_in"))
      (node (ref "U1") (pin "J10") (pinfunction "VSS6_J10") (pintype "power_in"))
      (node (ref "U1") (pin "J12") (pinfunction "VSS2_J12") (pintype "power_in"))
      (node (ref "U1") (pin "J14") (pinfunction "VSS_02_J14") (pintype "power_in"))
      (node (ref "U1") (pin "J7") (pinfunction "VSS_11_J7") (pintype "power_in"))
      (node (ref "U1") (pin "K10") (pinfunction "VSS8_K10") (pintype "power_in"))
      (node (ref "U1") (pin "K12") (pinfunction "VSS1_K12") (pintype "power_in"))
      (node (ref "U1") (pin "K6") (pinfunction "VSS_12_K6") (pintype "power_in"))
      (node (ref "U1") (pin "K7") (pinfunction "VSS9_K7") (pintype "power_in"))
      (node (ref "U1") (pin "L12") (pinfunction "VSS0_L12") (pintype "power_in"))
      (node (ref "U1") (pin "L7") (pinfunction "VSS_14_L7") (pintype "power_in"))
      (node (ref "U1") (pin "L8") (pinfunction "VSS_15_L8") (pintype "power_in"))
      (node (ref "U1") (pin "L9") (pinfunction "VSS10_L9") (pintype "power_in"))
      (node (ref "U1") (pin "M10") (pinfunction "VSS11_M10") (pintype "power_in"))
      (node (ref "U1") (pin "M17") (pinfunction "VSS_01_M17") (pintype "power_in"))
      (node (ref "U1") (pin "R3") (pinfunction "VSS_MIPI_R3") (pintype "power_in"))
      (node (ref "U1") (pin "T17") (pinfunction "VSS_USB_T17") (pintype "power_in"))
      (node (ref "U1") (pin "U4") (pinfunction "VSS_13_U4") (pintype "power_in"))
      (node (ref "X1") (pin "2") (pinfunction "2_2") (pintype "passive"))
      (node (ref "X1") (pin "4") (pinfunction "4_4") (pintype "passive"))
    )
    (net (code "23") (name "Net-(C22-Pad1)") (class "Default")
      (node (ref "C22") (pin "1") (pinfunction "1_1") (pintype "passive"))
      (node (ref "E56") (pin "1") (pinfunction "1_1") (pintype "passive"))
      (node (ref "X2") (pin "2") (pinfunction "2_2") (pintype "passive"))
    )
    (net (code "24") (name "Net-(C23-Pad1)") (class "Default")
      (node (ref "C23") (pin "1") (pinfunction "1_1") (pintype "passive"))
      (node (ref "E55") (pin "1") (pinfunction "1_1") (pintype "passive"))
      (node (ref "X2") (pin "1") (pinfunction "1_1") (pintype "passive"))
    )
    (net (code "25") (name "Net-(D16-A)") (class "Default")
      (node (ref "D16") (pin "2") (pinfunction "A_2") (pintype "passive"))
      (node (ref "E49") (pin "1") (pinfunction "1_1") (pintype "passive"))
    )
    (net (code "26") (name "Net-(R2-Pad2)") (class "Default")
      (node (ref "R2") (pin "2") (pinfunction "2_2") (pintype "passive"))
      (node (ref "TP2") (pin "1") (pinfunction "1_1") (pintype "passive"))
    )
    (net (code "27") (name "Net-(R2-Pad4)") (class "Default")
      (node (ref "R2") (pin "4") (pinfunction "4_4") (pintype "passive"))
      (node (ref "TP4") (pin "1") (pinfunction "1_1") (pintype "passive"))
    )
    (net (code "28") (name "Net-(R3-Pad2)") (class "Default")
      (node (ref "R3") (pin "2") (pinfunction "2_2") (pintype "passive"))
      (node (ref "TP3") (pin "1") (pinfunction "1_1") (pintype "passive"))
    )
    (net (code "29") (name "Net-(R3-Pad4)") (class "Default")
      (node (ref "R3") (pin "4") (pinfunction "4_4") (pintype "passive"))
      (node (ref "TP1") (pin "1") (pinfunction "1_1") (pintype "passive"))
    )
    (net (code "30") (name "Net-(U1D-VCC2_11)") (class "Default")
      (node (ref "C43") (pin "2") (pinfunction "2_2") (pintype "passive"))
      (node (ref "C44") (pin "2") (pinfunction "2_2") (pintype "passive"))
      (node (ref "C45") (pin "2") (pinfunction "2_2") (pintype "passive"))
      (node (ref "C46") (pin "2") (pinfunction "2_2") (pintype "passive"))
      (node (ref "C47") (pin "2") (pinfunction "2_2") (pintype "passive"))
      (node (ref "R58") (pin "1") (pinfunction "1_1") (pintype "passive"))
      (node (ref "U1") (pin "J6") (pinfunction "VCC2_11_J6") (pintype "power_in"))
      (node (ref "U1") (pin "L6") (pinfunction "VCC2_12_L6") (pintype "power_in"))
      (node (ref "U1") (pin "M7") (pinfunction "VCC2_14_M7") (pintype "power_in"))
      (node (ref "U1") (pin "M8") (pinfunction "VCC2_15_M8") (pintype "power_in"))
      (node (ref "U1") (pin "R1") (pinfunction "VCC2_13_R1") (pintype "power_in"))
    )
    (net (code "31") (name "P1.8V") (class "Default")
      (node (ref "C48") (pin "1") (pinfunction "1_1") (pintype "passive"))
      (node (ref "R86") (pin "1") (pinfunction "1_1") (pintype "passive"))
    )
    (net (code "32") (name "P3V3") (class "Default")
      (node (ref "E2") (pin "2") (pinfunction "2_2") (pintype "passive"))
      (node (ref "E3") (pin "2") (pinfunction "2_2") (pintype "passive"))
      (node (ref "E6") (pin "2") (pinfunction "2_2") (pintype "passive"))
      (node (ref "R2") (pin "1") (pinfunction "1_1") (pintype "passive"))
      (node (ref "R3") (pin "3") (pinfunction "3_3") (pintype "passive"))
    )
    (net (code "33") (name "P3V3_MCU") (class "Default")
      (node (ref "C1") (pin "2") (pinfunction "2_2") (pintype "passive"))
      (node (ref "C12") (pin "2") (pinfunction "2_2") (pintype "passive"))
      (node (ref "C13") (pin "2") (pinfunction "2_2") (pintype "passive"))
      (node (ref "C156") (pin "2") (pinfunction "2_2") (pintype "passive"))
      (node (ref "C17") (pin "2") (pinfunction "2_2") (pintype "passive"))
      (node (ref "C3") (pin "2") (pinfunction "2_2") (pintype "passive"))
      (node (ref "C4") (pin "2") (pinfunction "2_2") (pintype "passive"))
      (node (ref "C49") (pin "1") (pinfunction "1_1") (pintype "passive"))
      (node (ref "C5") (pin "2") (pinfunction "2_2") (pintype "passive"))
      (node (ref "C6") (pin "2") (pinfunction "2_2") (pintype "passive"))
      (node (ref "C7") (pin "2") (pinfunction "2_2") (pintype "passive"))
      (node (ref "E49") (pin "2") (pinfunction "2_2") (pintype "passive"))
      (node (ref "R3") (pin "1") (pinfunction "1_1") (pintype "passive"))
      (node (ref "R58") (pin "2") (pinfunction "2_2") (pintype "passive"))
      (node (ref "R9") (pin "1") (pinfunction "1_1") (pintype "passive"))
      (node (ref "R93") (pin "2") (pinfunction "2_2") (pintype "passive"))
      (node (ref "U1") (pin "F11") (pinfunction "VCC_07_F11") (pintype "power_in"))
      (node (ref "U1") (pin "F6") (pinfunction "VCC_08_F6") (pintype "power_in"))
      (node (ref "U1") (pin "G11") (pinfunction "VCC_06_G11") (pintype "power_in"))
      (node (ref "U1") (pin "G16") (pinfunction "VCC_05_G16") (pintype "power_in"))
      (node (ref "U1") (pin "G6") (pinfunction "VCC_09_G6") (pintype "power_in"))
      (node (ref "U1") (pin "H11") (pinfunction "VCC_04_H11") (pintype "power_in"))
      (node (ref "U1") (pin "H14") (pinfunction "VCC_03_H14") (pintype "power_in"))
      (node (ref "U1") (pin "H6") (pinfunction "VCC_10_H6") (pintype "power_in"))
      (node (ref "U1") (pin "K14") (pinfunction "VCC_02_K14") (pintype "power_in"))
      (node (ref "U1") (pin "L15") (pinfunction "VCC_01_L15") (pintype "power_in"))
    )
    (net (code "34") (name "P3V3_USB") (class "Default")
      (node (ref "C14") (pin "1") (pinfunction "1_1") (pintype "passive"))
      (node (ref "C15") (pin "1") (pinfunction "1_1") (pintype "passive"))
      (node (ref "C16") (pin "1") (pinfunction "1_1") (pintype "passive"))
      (node (ref "C20") (pin "1") (pinfunction "1_1") (pintype "passive"))
      (node (ref "L5") (pin "2") (pinfunction "2_2") (pintype "passive"))
      (node (ref "R2") (pin "3") (pinfunction "3_3") (pintype "passive"))
      (node (ref "U1") (pin "H15") (pinfunction "VCC_USBHS_H15") (pintype "power_in"))
      (node (ref "U1") (pin "U17") (pinfunction "VCC_USB_U17") (pintype "power_in"))
    )
    (net (code "35") (name "VBATT") (class "Default")
      (node (ref "C19") (pin "1") (pinfunction "1_1") (pintype "passive"))
      (node (ref "D15") (pin "1") (pinfunction "K_1") (pintype "passive"))
      (node (ref "D16") (pin "1") (pinfunction "K_1") (pintype "passive"))
      (node (ref "U1") (pin "M16") (pinfunction "VBATT_M16") (pintype "power_in"))
    )
    (net (code "36") (name "VBATT_IN") (class "Default")
      (node (ref "D15") (pin "2") (pinfunction "A_2") (pintype "passive"))
      (node (ref "J36") (pin "2") (pinfunction "2_2") (pintype "passive"))
    )
    (net (code "37") (name "VCC18_MIPI") (class "Default")
      (node (ref "R86") (pin "2") (pinfunction "2_2") (pintype "passive"))
      (node (ref "U1") (pin "R2") (pinfunction "VCC18_MIPI_R2") (pintype "power_in"))
    )
    (net (code "38") (name "VCC_DCDC") (class "Default")
      (node (ref "C78") (pin "1") (pinfunction "1_1") (pintype "passive"))
      (node (ref "C82") (pin "1") (pinfunction "1_1") (pintype "passive"))
      (node (ref "R93") (pin "1") (pinfunction "1_1") (pintype "passive"))
      (node (ref "U1") (pin "A10") (pinfunction "VCC_DCDC_A10") (pintype "power_in"))
      (node (ref "U1") (pin "A11") (pinfunction "VCC_DCDC_A11") (pintype "power_in"))
      (node (ref "U1") (pin "B10") (pinfunction "VCC_DCDC_B10") (pintype "power_in"))
      (node (ref "U1") (pin "B11") (pinfunction "VCC_DCDC_B11") (pintype "power_in"))
    )
    (net (code "39") (name "VCL") (class "Default")
      (node (ref "C50") (pin "1") (pinfunction "1_1") (pintype "passive"))
      (node (ref "C52") (pin "1") (pinfunction "1_1") (pintype "passive"))
      (node (ref "C53") (pin "1") (pinfunction "1_1") (pintype "passive"))
      (node (ref "C54") (pin "1") (pinfunction "1_1") (pintype "passive"))
      (node (ref "C55") (pin "1") (pinfunction "1_1") (pintype "passive"))
      (node (ref "C58") (pin "1") (pinfunction "1_1") (pintype "passive"))
      (node (ref "C59") (pin "1") (pinfunction "1_1") (pintype "passive"))
      (node (ref "C63") (pin "1") (pinfunction "1_1") (pintype "passive"))
      (node (ref "C73") (pin "1") (pinfunction "1_1") (pintype "passive"))
      (node (ref "C74") (pin "1") (pinfunction "1_1") (pintype "passive"))
      (node (ref "C75") (pin "1") (pinfunction "1_1") (pintype "passive"))
      (node (ref "C76") (pin "1") (pinfunction "1_1") (pintype "passive"))
      (node (ref "C77") (pin "1") (pinfunction "1_1") (pintype "passive"))
      (node (ref "L2") (pin "2") (pinfunction "2_2") (pintype "passive"))
      (node (ref "U1") (pin "F9") (pinfunction "VCL3_F9") (pintype "power_in"))
      (node (ref "U1") (pin "G9") (pinfunction "VCL4_G9") (pintype "power_in"))
      (node (ref "U1") (pin "H9") (pinfunction "VCL5_H9") (pintype "power_in"))
      (node (ref "U1") (pin "J11") (pinfunction "VCL2_J11") (pintype "power_in"))
      (node (ref "U1") (pin "J8") (pinfunction "VCL7_J8") (pintype "power_in"))
      (node (ref "U1") (pin "J9") (pinfunction "VCL6_J9") (pintype "power_in"))
      (node (ref "U1") (pin "K11") (pinfunction "VCL1_K11") (pintype "power_in"))
      (node (ref "U1") (pin "K8") (pinfunction "VCL9_K8") (pintype "power_in"))
      (node (ref "U1") (pin "K9") (pinfunction "VCL8_K9") (pintype "power_in"))
      (node (ref "U1") (pin "L10") (pinfunction "VCL10_L10") (pintype "power_in"))
      (node (ref "U1") (pin "L11") (pinfunction "VCL0_L11") (pintype "power_in"))
      (node (ref "U1") (pin "M11") (pinfunction "VCL11_M11") (pintype "power_in"))
    )
    (net (code "40") (name "VLO") (class "Default")
      (node (ref "L2") (pin "1") (pinfunction "1_1") (pintype "passive"))
      (node (ref "U1") (pin "A7") (pinfunction "VLO_A7") (pintype "power_in"))
      (node (ref "U1") (pin "A8") (pinfunction "VLO_A8") (pintype "power_in"))
      (node (ref "U1") (pin "B7") (pinfunction "VLO_B7") (pintype "power_in"))
      (node (ref "U1") (pin "B8") (pinfunction "VLO_B8") (pintype "power_in"))
    )
    (net (code "41") (name "VSS_DCDC") (class "Default")
      (node (ref "C77") (pin "2") (pinfunction "2_2") (pintype "passive"))
      (node (ref "C78") (pin "2") (pinfunction "2_2") (pintype "passive"))
      (node (ref "C82") (pin "2") (pinfunction "2_2") (pintype "passive"))
      (node (ref "FS2") (pin "1") (pinfunction "1_1") (pintype "passive"))
      (node (ref "U1") (pin "A9") (pinfunction "VSS_DCDC_A9") (pintype "power_in"))
      (node (ref "U1") (pin "B9") (pinfunction "VSS_DCDC_B9") (pintype "power_in"))
    )
    (net (code "42") (name "VSS_USBHS") (class "Default")
      (node (ref "C14") (pin "2") (pinfunction "2_2") (pintype "passive"))
      (node (ref "C15") (pin "2") (pinfunction "2_2") (pintype "passive"))
      (node (ref "C16") (pin "2") (pinfunction "2_2") (pintype "passive"))
      (node (ref "C20") (pin "2") (pinfunction "2_2") (pintype "passive"))
      (node (ref "C79") (pin "2") (pinfunction "2_2") (pintype "passive"))
      (node (ref "FS1") (pin "2") (pinfunction "2_2") (pintype "passive"))
      (node (ref "U1") (pin "J16") (pinfunction "VSS2_USBHS_J16") (pintype "power_in"))
      (node (ref "U1") (pin "J17") (pinfunction "VSS1_USBHS_J17") (pintype "power_in"))
    )
  )
)
